# 01_MCU.net
KiCad netlist of a schematic drawn in Altium Designer
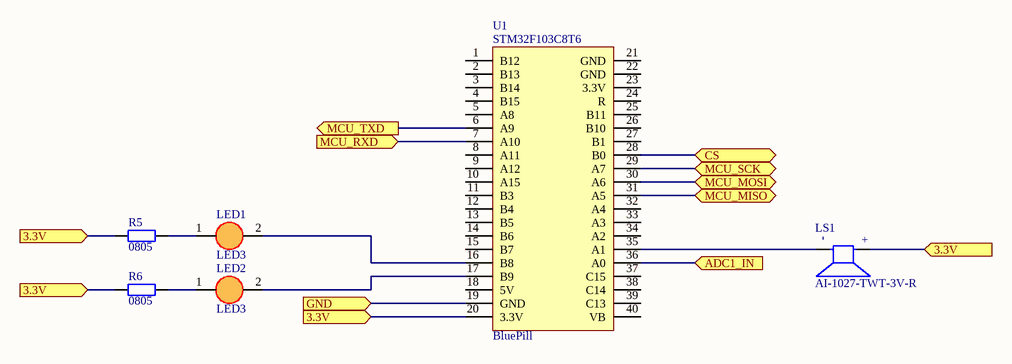
[diagram p0: 01_MCU.SchDoc]

(export (version "E")
  (design (tool "Eeschema 10.0.6"))
  (components
    (comp (ref "LED1")
      (value "LED3")
      (footprint "LED3mm")
      (description "LED 3mm")
      (libsource (lib "My Library") (part "LED 3mm"))
    )
    (comp (ref "LED2")
      (value "LED3")
      (footprint "LED3mm")
      (description "LED 3mm")
      (libsource (lib "My Library") (part "LED 3mm"))
    )
    (comp (ref "LS1")
      (value "AI-1027-TWT-3V-R")
      (footprint "XDCR_AI-1027-TWT-3V-R")
      (fields (field (name "MF") "PUI Audio, Inc."))
      (libsource (lib "AI-1027-TWT-3V-R") (part "AI-1027-TWT-3V-R"))
    )
    (comp (ref "R5")
      (value "0805")
      (footprint "DIEN TRO 0805")
      (description "Resistor SMD 0805")
      (fields (field (name "Comment") "R0805") (field (name "PUBLISHER") "Altium Limited"))
      (libsource (lib "My Library") (part "R0805"))
    )
    (comp (ref "R6")
      (value "0805")
      (footprint "DIEN TRO 0805")
      (description "Resistor SMD 0805")
      (fields (field (name "Comment") "R0805") (field (name "PUBLISHER") "Altium Limited"))
      (libsource (lib "My Library") (part "R0805"))
    )
    (comp (ref "U1")
      (value "BluePill")
      (footprint "DIP40 - duplicate")
      (libsource (lib "Bluepill") (part "BluePill"))
    )
  )
  (nets
    (net (code "1") (name "/3.3V") (class "Default")
      (node (ref "LS1") (pin "P") (pinfunction "P_P") (pintype "passive"))
      (node (ref "R5") (pin "1") (pinfunction "1_1") (pintype "passive"))
      (node (ref "R6") (pin "1") (pinfunction "1_1") (pintype "passive"))
      (node (ref "U1") (pin "20") (pinfunction "3.3V_20") (pintype "passive"))
    )
    (net (code "2") (name "/ADC1_IN") (class "Default")
      (node (ref "U1") (pin "36") (pinfunction "A0_36") (pintype "passive"))
    )
    (net (code "3") (name "/CS") (class "Default")
      (node (ref "U1") (pin "28") (pinfunction "B0_28") (pintype "passive"))
    )
    (net (code "4") (name "/GND") (class "Default")
      (node (ref "U1") (pin "19") (pinfunction "GND_19") (pintype "passive"))
    )
    (net (code "5") (name "/MCU_MISO") (class "Default")
      (node (ref "U1") (pin "31") (pinfunction "A5_31") (pintype "passive"))
    )
    (net (code "6") (name "/MCU_MOSI") (class "Default")
      (node (ref "U1") (pin "30") (pinfunction "A6_30") (pintype "passive"))
    )
    (net (code "7") (name "/MCU_RXD") (class "Default")
      (node (ref "U1") (pin "7") (pinfunction "A10_7") (pintype "passive"))
    )
    (net (code "8") (name "/MCU_SCK") (class "Default")
      (node (ref "U1") (pin "29") (pinfunction "A7_29") (pintype "passive"))
    )
    (net (code "9") (name "/MCU_TXD") (class "Default")
      (node (ref "U1") (pin "6") (pinfunction "A9_6") (pintype "passive"))
    )
    (net (code "10") (name "Net-(LED1-A)") (class "Default")
      (node (ref "LED1") (pin "1") (pinfunction "A_1") (pintype "passive"))
      (node (ref "R5") (pin "2") (pinfunction "2_2") (pintype "passive"))
    )
    (net (code "11") (name "Net-(LED1-K)") (class "Default")
      (node (ref "LED1") (pin "2") (pinfunction "K_2") (pintype "passive"))
      (node (ref "U1") (pin "16") (pinfunction "B8_16") (pintype "passive"))
    )
    (net (code "12") (name "Net-(LED2-A)") (class "Default")
      (node (ref "LED2") (pin "1") (pinfunction "A_1") (pintype "passive"))
      (node (ref "R6") (pin "2") (pinfunction "2_2") (pintype "passive"))
    )
    (net (code "13") (name "Net-(LED2-K)") (class "Default")
      (node (ref "LED2") (pin "2") (pinfunction "K_2") (pintype "passive"))
      (node (ref "U1") (pin "17") (pinfunction "B9_17") (pintype "passive"))
    )
    (net (code "14") (name "Net-(U1-A1)") (class "Default")
      (node (ref "LS1") (pin "N") (pinfunction "N_N") (pintype "passive"))
      (node (ref "U1") (pin "35") (pinfunction "A1_35") (pintype "passive"))
    )
    (net (code "15") (name "unconnected-(U1-3.3V-Pad23)") (class "Default")
      (node (ref "U1") (pin "23") (pinfunction "3.3V_23") (pintype "passive"))
    )
    (net (code "16") (name "unconnected-(U1-5V-Pad18)") (class "Default")
      (node (ref "U1") (pin "18") (pinfunction "5V_18") (pintype "passive"))
    )
    (net (code "17") (name "unconnected-(U1-A2-Pad34)") (class "Default")
      (node (ref "U1") (pin "34") (pinfunction "A2_34") (pintype "passive"))
    )
    (net (code "18") (name "unconnected-(U1-A3-Pad33)") (class "Default")
      (node (ref "U1") (pin "33") (pinfunction "A3_33") (pintype "passive"))
    )
    (net (code "19") (name "unconnected-(U1-A4-Pad32)") (class "Default")
      (node (ref "U1") (pin "32") (pinfunction "A4_32") (pintype "passive"))
    )
    (net (code "20") (name "unconnected-(U1-A8-Pad5)") (class "Default")
      (node (ref "U1") (pin "5") (pinfunction "A8_5") (pintype "passive"))
    )
    (net (code "21") (name "unconnected-(U1-A11-Pad8)") (class "Default")
      (node (ref "U1") (pin "8") (pinfunction "A11_8") (pintype "passive"))
    )
    (net (code "22") (name "unconnected-(U1-A12-Pad9)") (class "Default")
      (node (ref "U1") (pin "9") (pinfunction "A12_9") (pintype "passive"))
    )
    (net (code "23") (name "unconnected-(U1-A15-Pad10)") (class "Default")
      (node (ref "U1") (pin "10") (pinfunction "A15_10") (pintype "passive"))
    )
    (net (code "24") (name "unconnected-(U1-B1-Pad27)") (class "Default")
      (node (ref "U1") (pin "27") (pinfunction "B1_27") (pintype "passive"))
    )
    (net (code "25") (name "unconnected-(U1-B3-Pad11)") (class "Default")
      (node (ref "U1") (pin "11") (pinfunction "B3_11") (pintype "passive"))
    )
    (net (code "26") (name "unconnected-(U1-B4-Pad12)") (class "Default")
      (node (ref "U1") (pin "12") (pinfunction "B4_12") (pintype "passive"))
    )
    (net (code "27") (name "unconnected-(U1-B5-Pad13)") (class "Default")
      (node (ref "U1") (pin "13") (pinfunction "B5_13") (pintype "passive"))
    )
    (net (code "28") (name "unconnected-(U1-B6-Pad14)") (class "Default")
      (node (ref "U1") (pin "14") (pinfunction "B6_14") (pintype "passive"))
    )
    (net (code "29") (name "unconnected-(U1-B7-Pad15)") (class "Default")
      (node (ref "U1") (pin "15") (pinfunction "B7_15") (pintype "passive"))
    )
    (net (code "30") (name "unconnected-(U1-B10-Pad26)") (class "Default")
      (node (ref "U1") (pin "26") (pinfunction "B10_26") (pintype "passive"))
    )
    (net (code "31") (name "unconnected-(U1-B11-Pad25)") (class "Default")
      (node (ref "U1") (pin "25") (pinfunction "B11_25") (pintype "passive"))
    )
    (net (code "32") (name "unconnected-(U1-B12-Pad1)") (class "Default")
      (node (ref "U1") (pin "1") (pinfunction "B12_1") (pintype "passive"))
    )
    (net (code "33") (name "unconnected-(U1-B13-Pad2)") (class "Default")
      (node (ref "U1") (pin "2") (pinfunction "B13_2") (pintype "passive"))
    )
    (net (code "34") (name "unconnected-(U1-B14-Pad3)") (class "Default")
      (node (ref "U1") (pin "3") (pinfunction "B14_3") (pintype "passive"))
    )
    (net (code "35") (name "unconnected-(U1-B15-Pad4)") (class "Default")
      (node (ref "U1") (pin "4") (pinfunction "B15_4") (pintype "passive"))
    )
    (net (code "36") (name "unconnected-(U1-C13-Pad39)") (class "Default")
      (node (ref "U1") (pin "39") (pinfunction "C13_39") (pintype "passive"))
    )
    (net (code "37") (name "unconnected-(U1-C14-Pad38)") (class "Default")
      (node (ref "U1") (pin "38") (pinfunction "C14_38") (pintype "passive"))
    )
    (net (code "38") (name "unconnected-(U1-C15-Pad37)") (class "Default")
      (node (ref "U1") (pin "37") (pinfunction "C15_37") (pintype "passive"))
    )
    (net (code "39") (name "unconnected-(U1-GND-Pad21)") (class "Default")
      (node (ref "U1") (pin "21") (pinfunction "GND_21") (pintype "passive"))
    )
    (net (code "40") (name "unconnected-(U1-GND-Pad22)") (class "Default")
      (node (ref "U1") (pin "22") (pinfunction "GND_22") (pintype "passive"))
    )
    (net (code "41") (name "unconnected-(U1-R-Pad24)") (class "Default")
      (node (ref "U1") (pin "24") (pinfunction "R_24") (pintype "passive"))
    )
    (net (code "42") (name "unconnected-(U1-VB-Pad40)") (class "Default")
      (node (ref "U1") (pin "40") (pinfunction "VB_40") (pintype "passive"))
    )
  )
)
